# DIOT_PSU_Mezzanine.net
KiCad netlist of a schematic drawn in Altium Designer
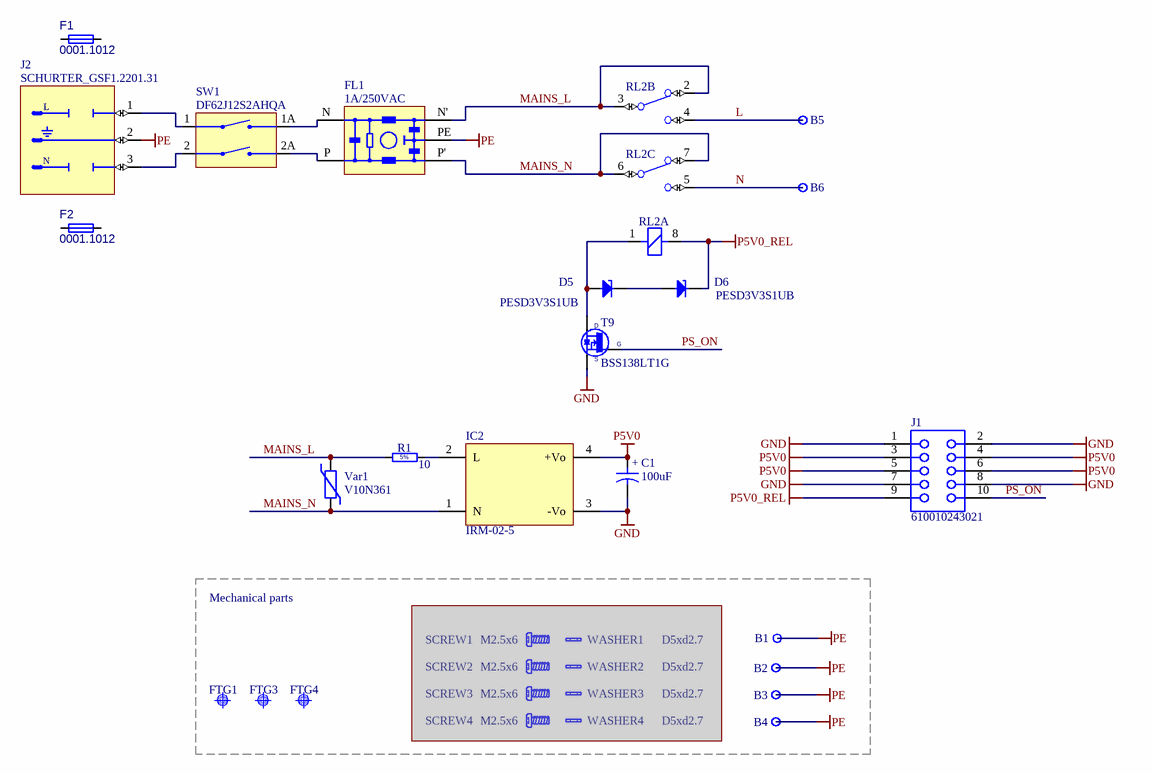
[diagram p0: DIOT_PSU_Mezzanine.SchDoc]

(export (version "E")
  (design (tool "Eeschema 10.0.6"))
  (components
    (comp (ref "B1")
      (value "Plated Hole")
      (footprint "MTG320_550")
      (description "Single Terminal Socket")
      (fields (field (name "PART NUMBER") "PLATED_HOLE3.2_PAD5.5") (field (name "AUTHOR") "CERN DEM JMW"))
      (libsource (lib "Eletro-mechanical") (part "Single Terminal Socket"))
    )
    (comp (ref "B2")
      (value "Plated Hole")
      (footprint "MTG320_550")
      (description "Single Terminal Socket")
      (fields (field (name "PART NUMBER") "PLATED_HOLE3.2_PAD5.5") (field (name "AUTHOR") "CERN DEM JMW"))
      (libsource (lib "Eletro-mechanical") (part "Single Terminal Socket"))
    )
    (comp (ref "B3")
      (value "Plated Hole")
      (footprint "MTG320_550")
      (description "Single Terminal Socket")
      (fields (field (name "PART NUMBER") "PLATED_HOLE3.2_PAD5.5") (field (name "AUTHOR") "CERN DEM JMW"))
      (libsource (lib "Eletro-mechanical") (part "Single Terminal Socket"))
    )
    (comp (ref "B4")
      (value "Plated Hole")
      (footprint "MTG320_550")
      (description "Single Terminal Socket")
      (fields (field (name "PART NUMBER") "PLATED_HOLE3.2_PAD5.5") (field (name "AUTHOR") "CERN DEM JMW"))
      (libsource (lib "Eletro-mechanical") (part "Single Terminal Socket"))
    )
    (comp (ref "B5")
      (value "Plated Hole")
      (footprint "c350h200")
      (description "Single Terminal Socket")
      (fields (field (name "PART NUMBER") "PLATED_HOLE2.0_PAD3.5") (field (name "AUTHOR") "CERN DEM JMW"))
      (libsource (lib "Eletro-mechanical") (part "Single Terminal Socket"))
    )
    (comp (ref "B6")
      (value "Plated Hole")
      (footprint "c350h200")
      (description "Single Terminal Socket")
      (fields (field (name "PART NUMBER") "PLATED_HOLE2.0_PAD3.5") (field (name "AUTHOR") "CERN DEM JMW"))
      (libsource (lib "Eletro-mechanical") (part "Single Terminal Socket"))
    )
    (comp (ref "C1")
      (value "100uF")
      (footprint "CAPPR350-850X600")
      (description "Polarised capacitor")
      (fields
        (field (name "PART NUMBER") "CAER_100UF_10V_20%_350-850X600_LESR0R032")
        (field (name "VOLTAGE") "10V")
        (field (name "AUTHOR") "CERN DEM JLC")
      )
      (libsource (lib "Capacitors") (part "Capacitor - polarized"))
    )
    (comp (ref "D5")
      (value "PESD3V3S1UB")
      (footprint "SODFL1608X65N")
      (description "ESD protection diode")
      (fields
        (field (name "VOLTAGE") "3V3")
        (field (name "POWER") "330W")
        (field (name "AUTHOR") "CERN DEM JLC")
      )
      (libsource (lib "ICs And Semiconductors") (part "Diode ESD"))
    )
    (comp (ref "D6")
      (value "PESD3V3S1UB")
      (footprint "SODFL1608X65N")
      (description "ESD protection diode")
      (fields
        (field (name "VOLTAGE") "3V3")
        (field (name "POWER") "330W")
        (field (name "AUTHOR") "CERN DEM JLC")
      )
      (libsource (lib "ICs And Semiconductors") (part "Diode ESD"))
    )
    (comp (ref "F1")
      (value "0001.1012")
      (footprint "0001.1012")
      (description "Electric Fuse, Very Fast Blow, 6.3A, 250VAC, 1500A (IR), Inline/holder, 5x20mm")
      (libsource (lib "TechnoSystem Workspace") (part "Fuse No Pin"))
    )
    (comp (ref "F2")
      (value "0001.1012")
      (footprint "0001.1012")
      (description "Electric Fuse, Very Fast Blow, 6.3A, 250VAC, 1500A (IR), Inline/holder, 5x20mm")
      (libsource (lib "TechnoSystem Workspace") (part "Fuse No Pin"))
    )
    (comp (ref "FL1")
      (value "1A/250VAC")
      (footprint "FIL_SCHAFFNER_FN 406")
      (description "0.6 to 8.4A 230VAC Single Phase Ultra Compact EMC Filter")
      (fields
        (field (name "PART NUMBER") "FIL_SCHAFFNER_FN406-3-02")
        (field (name "MANUFACTURER") "SCHAFFNER")
        (field (name "AUTHOR") "CERN DEM JLC")
      )
      (libsource (lib "Inductors & Transformers") (part "FIL_SCHAFFNER_FN 406"))
    )
    (comp (ref "FTG1")
      (value "Use only in PCB")
      (footprint "FIDUCIAL_TOP_C100-200")
      (description "Fiducial Target")
      (fields (field (name "PART NUMBER") "FIDUCIAL_TARGET_C100-200") (field (name "AUTHOR") "CERN DEM JLC"))
      (libsource (lib "Eletro-mechanical") (part "Fiducial Target"))
    )
    (comp (ref "FTG3")
      (value "Use only in PCB")
      (footprint "FIDUCIAL_TOP_C100-200")
      (description "Fiducial Target")
      (fields (field (name "PART NUMBER") "FIDUCIAL_TARGET_C100-200") (field (name "AUTHOR") "CERN DEM JLC"))
      (libsource (lib "Eletro-mechanical") (part "Fiducial Target"))
    )
    (comp (ref "FTG4")
      (value "Use only in PCB")
      (footprint "FIDUCIAL_TOP_S100-200")
      (description "Fiducial Target")
      (fields (field (name "PART NUMBER") "FIDUCIAL_TARGET_S100-200") (field (name "AUTHOR") "CERN DEM JLC"))
      (libsource (lib "Eletro-mechanical") (part "Fiducial Target"))
    )
    (comp (ref "IC2")
      (value "IRM-02-5")
      (footprint "PWS_MEANWELL_IRM-02")
      (description "Power Supply")
      (fields (field (name "MANUFACTURER") "MEAN WELL") (field (name "AUTHOR") "GK"))
      (libsource (lib "Regulators_SMPS") (part "AC_DC_IRM-02-5"))
    )
    (comp (ref "J1")
      (value "610010243021")
      (footprint "610010243021")
      (description "WR-PHD Socket Header, SMT, Vertical, pitch 2.54mm, 2 Row, 10P")
      (fields
        (field (name "MANUFACTURER PART NUMBER") "610010243021")
        (field (name "MANUFACTURER") "Wurth Elektronik")
      )
      (libsource (lib "Altium_WR-PHD (rev24a) (4)") (part "610010243021"))
    )
    (comp (ref "J2")
      (value "IEC")
      (footprint "SCHURTER_GSF1.2202.31")
      (description "Connector 3 Male 2P+ 2 Fuse Holder")
      (fields
        (field (name "PART NUMBER") "SCHURTER_GSF1.2201.31")
        (field (name "MANUFACTURER") "SCHURTER")
        (field (name "MANUFACTURER PART NUMBER") "GSF1.2201.31")
        (field (name "AUTHOR") "CERN DEM JMW")
      )
      (libsource (lib "Connectors") (part "Connector 3 Male 2P+T+2FUSH"))
    )
    (comp (ref "R1")
      (value "10")
      (footprint "RESADV508-1670X520")
      (description "Resistor - 5%")
      (fields
        (field (name "PART NUMBER") "RMF_10R_5%_3W_250PPM_508-1670X520_v")
        (field (name "POWER") "3W")
        (field (name "AUTHOR") "CERN DEM JLC")
      )
      (libsource (lib "Resistors") (part "Resistor - 5%"))
    )
    (comp (ref "RL2")
      (value "REL_OMRON_G2RL-24")
      (footprint "REL_OMRON_G2RL-24")
      (description "DPDT Power Relay, G2RL Series")
      (fields
        (field (name "PART NUMBER") "REL_OMRON_G2RL-24-DC5")
        (field (name "MANUFACTURER") "OMRON ELECTRONIC")
        (field (name "AUTHOR") "CERN DEM BC")
      )
      (libsource (lib "Eletro-mechanical") (part "REL_OMRON_G2RL-24"))
    )
    (comp (ref "SCREW1")
      (value "M2.5x6")
      (footprint "BOSSARD_BN5687-3061597_v")
      (description "Screw")
      (fields
        (field (name "PART NUMBER") "BOSSARD_BN5687-3061597_v")
        (field (name "MANUFACTURER") "BOSSARD")
        (field (name "AUTHOR") "CERN DEM JLC")
      )
      (libsource (lib "Eletro-mechanical") (part "Screw"))
    )
    (comp (ref "SCREW2")
      (value "M2.5x6")
      (footprint "BOSSARD_BN5687-3061597_v")
      (description "Screw")
      (fields
        (field (name "PART NUMBER") "BOSSARD_BN5687-3061597_v")
        (field (name "MANUFACTURER") "BOSSARD")
        (field (name "AUTHOR") "CERN DEM JLC")
      )
      (libsource (lib "Eletro-mechanical") (part "Screw"))
    )
    (comp (ref "SCREW3")
      (value "M2.5x6")
      (footprint "BOSSARD_BN5687-3061597_v")
      (description "Screw")
      (fields
        (field (name "PART NUMBER") "BOSSARD_BN5687-3061597_v")
        (field (name "MANUFACTURER") "BOSSARD")
        (field (name "AUTHOR") "CERN DEM JLC")
      )
      (libsource (lib "Eletro-mechanical") (part "Screw"))
    )
    (comp (ref "SCREW4")
      (value "M2.5x6")
      (footprint "BOSSARD_BN5687-3061597_v")
      (description "Screw")
      (fields
        (field (name "PART NUMBER") "BOSSARD_BN5687-3061597_v")
        (field (name "MANUFACTURER") "BOSSARD")
        (field (name "AUTHOR") "CERN DEM JLC")
      )
      (libsource (lib "Eletro-mechanical") (part "Screw"))
    )
    (comp (ref "SW1")
      (value "DF62J12S2AHQA")
      (footprint "DF62J12S2AHQA")
      (description "Rocker Switch DPST 16A (AC), 6A (DC) 125 V Panel Mount, Snap-In, Right Angle")
      (fields
        (field (name "TOLERANCE") "±1%")
        (field (name "MANUFACTURER") "C&K")
        (field (name "AUTHOR") "LPA")
      )
      (libsource (lib "DIOT_PSU_integrated") (part "DF62J12S2AHQA"))
    )
    (comp (ref "T9")
      (value "BSS138LT1G")
      (footprint "SOT95P240X110-3N")
      (description "N-CHANNEL MOSFET WITH DIODE")
      (fields
        (field (name "MANUFACTURER") "ON SEMICONDUCTOR")
        (field (name "MANUFACTURER PART NUMBER") "BSS138L")
        (field (name "AUTHOR") "CERN DEM JLC")
      )
      (libsource (lib "ICs And Semiconductors") (part "N-MOSFET-D 1G 2S 3D"))
    )
    (comp (ref "Var1")
      (value "V10N361")
      (footprint "VARISTOR THT")
      (description "Warystor fi10mm 360V")
      (libsource (lib "Component Library 3.2") (part "V10N361"))
    )
    (comp (ref "WASHER1")
      (value "D5xd2.7")
      (footprint "BOSSARD_BN678-8303525_v")
      (description "Washer")
      (fields
        (field (name "PART NUMBER") "BOSSARD_BN678-8303525_v")
        (field (name "MANUFACTURER") "BOSSARD")
        (field (name "AUTHOR") "CERN DEM JLC")
      )
      (libsource (lib "Eletro-mechanical") (part "Washer"))
    )
    (comp (ref "WASHER2")
      (value "D5xd2.7")
      (footprint "BOSSARD_BN678-8303525_v")
      (description "Washer")
      (fields
        (field (name "PART NUMBER") "BOSSARD_BN678-8303525_v")
        (field (name "MANUFACTURER") "BOSSARD")
        (field (name "AUTHOR") "CERN DEM JLC")
      )
      (libsource (lib "Eletro-mechanical") (part "Washer"))
    )
    (comp (ref "WASHER3")
      (value "D5xd2.7")
      (footprint "BOSSARD_BN678-8303525_v")
      (description "Washer")
      (fields
        (field (name "PART NUMBER") "BOSSARD_BN678-8303525_v")
        (field (name "MANUFACTURER") "BOSSARD")
        (field (name "AUTHOR") "CERN DEM JLC")
      )
      (libsource (lib "Eletro-mechanical") (part "Washer"))
    )
    (comp (ref "WASHER4")
      (value "D5xd2.7")
      (footprint "BOSSARD_BN678-8303525_v")
      (description "Washer")
      (fields
        (field (name "PART NUMBER") "BOSSARD_BN678-8303525_v")
        (field (name "MANUFACTURER") "BOSSARD")
        (field (name "AUTHOR") "CERN DEM JLC")
      )
      (libsource (lib "Eletro-mechanical") (part "Washer"))
    )
  )
  (nets
    (net (code "1") (name "/L") (class "Default")
      (node (ref "B5") (pin "1") (pinfunction "1_1") (pintype "bidirectional"))
      (node (ref "RL2") (pin "4") (pinfunction "NO_4") (pintype "bidirectional"))
    )
    (net (code "2") (name "/MAINS_L") (class "Default")
      (node (ref "FL1") (pin "N'") (pinfunction "N'_N'") (pintype "power_in"))
      (node (ref "R1") (pin "2") (pinfunction "2_2") (pintype "passive"))
      (node (ref "RL2") (pin "2") (pinfunction "NC_2") (pintype "bidirectional"))
      (node (ref "RL2") (pin "3") (pinfunction "C_3") (pintype "bidirectional"))
      (node (ref "Var1") (pin "2") (pinfunction "2_2") (pintype "passive"))
    )
    (net (code "3") (name "/MAINS_N") (class "Default")
      (node (ref "FL1") (pin "P'") (pinfunction "P'_P'") (pintype "passive"))
      (node (ref "IC2") (pin "1") (pinfunction "N_1") (pintype "power_in"))
      (node (ref "RL2") (pin "6") (pinfunction "C_6") (pintype "bidirectional"))
      (node (ref "RL2") (pin "7") (pinfunction "NC_7") (pintype "bidirectional"))
      (node (ref "Var1") (pin "1") (pinfunction "1_1") (pintype "passive"))
    )
    (net (code "4") (name "/N") (class "Default")
      (node (ref "B6") (pin "1") (pinfunction "1_1") (pintype "bidirectional"))
      (node (ref "RL2") (pin "5") (pinfunction "NO_5") (pintype "bidirectional"))
    )
    (net (code "5") (name "/PS_ON") (class "Default")
      (node (ref "J1") (pin "10") (pinfunction "10_10") (pintype "passive"))
      (node (ref "T9") (pin "1") (pinfunction "G_1") (pintype "passive"))
    )
    (net (code "6") (name "GND") (class "Default")
      (node (ref "C1") (pin "2") (pinfunction "2_2") (pintype "passive"))
      (node (ref "IC2") (pin "3") (pinfunction "-Vo_3") (pintype "power_in"))
      (node (ref "J1") (pin "1") (pinfunction "1_1") (pintype "passive"))
      (node (ref "J1") (pin "2") (pinfunction "2_2") (pintype "passive"))
      (node (ref "J1") (pin "7") (pinfunction "7_7") (pintype "passive"))
      (node (ref "J1") (pin "8") (pinfunction "8_8") (pintype "passive"))
      (node (ref "T9") (pin "2") (pinfunction "S_2") (pintype "passive"))
    )
    (net (code "7") (name "Net-(D5-A)") (class "Default")
      (node (ref "D5") (pin "2") (pinfunction "A_2") (pintype "passive"))
      (node (ref "RL2") (pin "1") (pinfunction "1_1") (pintype "passive"))
      (node (ref "T9") (pin "3") (pinfunction "D_3") (pintype "passive"))
    )
    (net (code "8") (name "Net-(D5-C)") (class "Default")
      (node (ref "D5") (pin "1") (pinfunction "C_1") (pintype "passive"))
      (node (ref "D6") (pin "2") (pinfunction "A_2") (pintype "passive"))
    )
    (net (code "9") (name "Net-(FL1-PadN)") (class "Default")
      (node (ref "FL1") (pin "N") (pinfunction "N_N") (pintype "passive"))
      (node (ref "SW1") (pin "1A") (pinfunction "1A_1A") (pintype "passive"))
    )
    (net (code "10") (name "Net-(FL1-PadP)") (class "Default")
      (node (ref "FL1") (pin "P") (pinfunction "P_P") (pintype "passive"))
      (node (ref "SW1") (pin "2A") (pinfunction "2A_2A") (pintype "passive"))
    )
    (net (code "11") (name "Net-(IC2-L)") (class "Default")
      (node (ref "IC2") (pin "2") (pinfunction "L_2") (pintype "power_in"))
      (node (ref "R1") (pin "1") (pinfunction "1_1") (pintype "passive"))
    )
    (net (code "12") (name "Net-(J2-Pad1)") (class "Default")
      (node (ref "J2") (pin "1") (pinfunction "1_1") (pintype "bidirectional"))
      (node (ref "SW1") (pin "1") (pinfunction "1_1") (pintype "passive"))
    )
    (net (code "13") (name "Net-(J2-Pad3)") (class "Default")
      (node (ref "J2") (pin "3") (pinfunction "3_3") (pintype "bidirectional"))
      (node (ref "SW1") (pin "2") (pinfunction "2_2") (pintype "passive"))
    )
    (net (code "14") (name "P5V0") (class "Default")
      (node (ref "C1") (pin "1") (pinfunction "1_1") (pintype "passive"))
      (node (ref "IC2") (pin "4") (pinfunction "+Vo_4") (pintype "power_in"))
      (node (ref "J1") (pin "3") (pinfunction "3_3") (pintype "passive"))
      (node (ref "J1") (pin "4") (pinfunction "4_4") (pintype "passive"))
      (node (ref "J1") (pin "5") (pinfunction "5_5") (pintype "passive"))
      (node (ref "J1") (pin "6") (pinfunction "6_6") (pintype "passive"))
    )
    (net (code "15") (name "P5V0_REL") (class "Default")
      (node (ref "D6") (pin "1") (pinfunction "C_1") (pintype "passive"))
      (node (ref "J1") (pin "9") (pinfunction "9_9") (pintype "passive"))
      (node (ref "RL2") (pin "8") (pinfunction "8_8") (pintype "passive"))
    )
    (net (code "16") (name "PE") (class "Default")
      (node (ref "B1") (pin "1") (pinfunction "1_1") (pintype "bidirectional"))
      (node (ref "B2") (pin "1") (pinfunction "1_1") (pintype "bidirectional"))
      (node (ref "B3") (pin "1") (pinfunction "1_1") (pintype "bidirectional"))
      (node (ref "B4") (pin "1") (pinfunction "1_1") (pintype "bidirectional"))
      (node (ref "FL1") (pin "PE") (pinfunction "PE_PE") (pintype "passive"))
      (node (ref "J2") (pin "2") (pinfunction "2_2") (pintype "bidirectional"))
    )
  )
)
